# Breakout.net
KiCad netlist of a schematic drawn in EAGLE
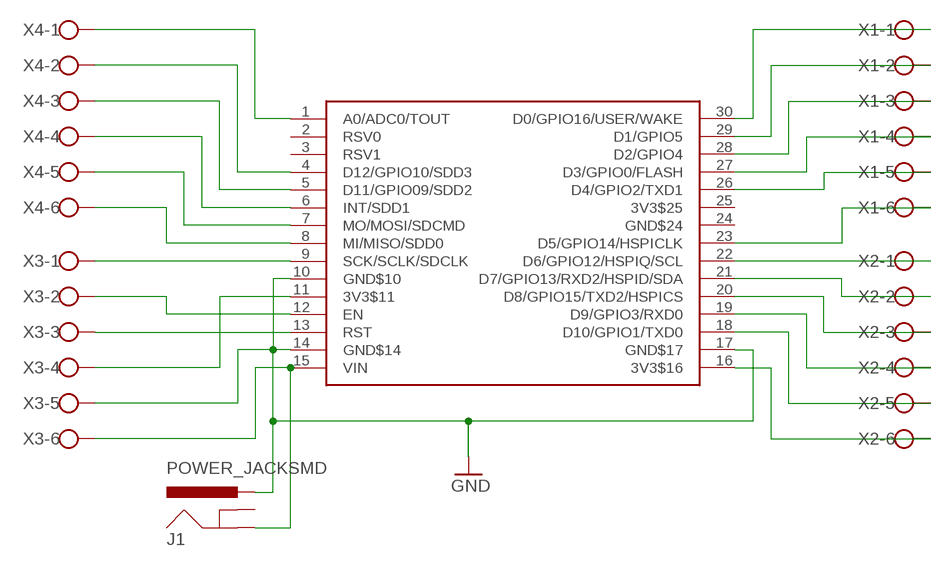
[diagram p0: schematic, sheet 1]

(export (version "E")
  (design (tool "Eeschema 10.0.6"))
  (components
    (comp (ref "J1")
      (value "POWER_JACKSMD")
      (footprint "eagle-import:POWER_JACK_SMD")
      (libsource (lib "eagle-import") (part "POWER_JACKSMD"))
    )
    (comp (ref "U$1")
      (value "NERDSHIELD")
      (footprint "eagle-import:NERDUINO_STACK")
      (libsource (lib "eagle-import") (part "NERDSHIELD"))
    )
    (comp (ref "X1")
      (value "W237-6")
      (footprint "eagle-import:W237-6")
      (libsource (lib "eagle-import") (part "W237-6"))
    )
    (comp (ref "X2")
      (value "W237-6")
      (footprint "eagle-import:W237-6")
      (libsource (lib "eagle-import") (part "W237-6"))
    )
    (comp (ref "X3")
      (value "W237-6")
      (footprint "eagle-import:W237-6")
      (libsource (lib "eagle-import") (part "W237-6"))
    )
    (comp (ref "X4")
      (value "W237-6")
      (footprint "eagle-import:W237-6")
      (libsource (lib "eagle-import") (part "W237-6"))
    )
  )
  (nets
    (net (code "1") (name "GND") (class "Default")
      (node (ref "J1") (pin "VIN0") (pinfunction "PWR_VIN0") (pintype "bidirectional"))
      (node (ref "U$1") (pin "10") (pinfunction "GND$10_10") (pintype "bidirectional"))
      (node (ref "U$1") (pin "14") (pinfunction "GND$14_14") (pintype "bidirectional"))
      (node (ref "U$1") (pin "17") (pinfunction "GND$17_17") (pintype "bidirectional"))
      (node (ref "X3") (pin "5") (pinfunction "KL_5") (pintype "passive"))
    )
    (net (code "2") (name "Net-(J1-GND)") (class "Default")
      (node (ref "J1") (pin "P$4") (pinfunction "GND_P$4") (pintype "bidirectional"))
      (node (ref "U$1") (pin "15") (pinfunction "VIN_15") (pintype "bidirectional"))
      (node (ref "X3") (pin "6") (pinfunction "KL_6") (pintype "passive"))
    )
    (net (code "3") (name "Net-(U$1-3V3$11)") (class "Default")
      (node (ref "U$1") (pin "11") (pinfunction "3V3$11_11") (pintype "bidirectional"))
      (node (ref "X3") (pin "4") (pinfunction "KL_4") (pintype "passive"))
    )
    (net (code "4") (name "Net-(U$1-3V3$16)") (class "Default")
      (node (ref "U$1") (pin "16") (pinfunction "3V3$16_16") (pintype "bidirectional"))
      (node (ref "X2") (pin "6") (pinfunction "KL_6") (pintype "passive"))
    )
    (net (code "5") (name "Net-(U$1-A0{slash}ADC0{slash}TOUT)") (class "Default")
      (node (ref "U$1") (pin "1") (pinfunction "A0/ADC0/TOUT_1") (pintype "bidirectional"))
      (node (ref "X4") (pin "1") (pinfunction "KL_1") (pintype "passive"))
    )
    (net (code "6") (name "Net-(U$1-D0{slash}GPIO16{slash}USER{slash}WAKE)") (class "Default")
      (node (ref "U$1") (pin "30") (pinfunction "D0/GPIO16/USER/WAKE_30") (pintype "bidirectional"))
      (node (ref "X1") (pin "1") (pinfunction "KL_1") (pintype "passive"))
    )
    (net (code "7") (name "Net-(U$1-D1{slash}GPIO5)") (class "Default")
      (node (ref "U$1") (pin "29") (pinfunction "D1/GPIO5_29") (pintype "bidirectional"))
      (node (ref "X1") (pin "2") (pinfunction "KL_2") (pintype "passive"))
    )
    (net (code "8") (name "Net-(U$1-D2{slash}GPIO4)") (class "Default")
      (node (ref "U$1") (pin "28") (pinfunction "D2/GPIO4_28") (pintype "bidirectional"))
      (node (ref "X1") (pin "3") (pinfunction "KL_3") (pintype "passive"))
    )
    (net (code "9") (name "Net-(U$1-D3{slash}GPIO0{slash}FLASH)") (class "Default")
      (node (ref "U$1") (pin "27") (pinfunction "D3/GPIO0/FLASH_27") (pintype "bidirectional"))
      (node (ref "X1") (pin "4") (pinfunction "KL_4") (pintype "passive"))
    )
    (net (code "10") (name "Net-(U$1-D4{slash}GPIO2{slash}TXD1)") (class "Default")
      (node (ref "U$1") (pin "26") (pinfunction "D4/GPIO2/TXD1_26") (pintype "bidirectional"))
      (node (ref "X1") (pin "5") (pinfunction "KL_5") (pintype "passive"))
    )
    (net (code "11") (name "Net-(U$1-D5{slash}GPIO14{slash}HSPICLK)") (class "Default")
      (node (ref "U$1") (pin "23") (pinfunction "D5/GPIO14/HSPICLK_23") (pintype "bidirectional"))
      (node (ref "X1") (pin "6") (pinfunction "KL_6") (pintype "passive"))
    )
    (net (code "12") (name "Net-(U$1-D6{slash}GPIO12{slash}HSPIQ{slash}SCL)") (class "Default")
      (node (ref "U$1") (pin "22") (pinfunction "D6/GPIO12/HSPIQ/SCL_22") (pintype "bidirectional"))
      (node (ref "X2") (pin "1") (pinfunction "KL_1") (pintype "passive"))
    )
    (net (code "13") (name "Net-(U$1-D7{slash}GPIO13{slash}RXD2{slash}HSPID{slash}SDA)") (class "Default")
      (node (ref "U$1") (pin "21") (pinfunction "D7/GPIO13/RXD2/HSPID/SDA_21") (pintype "bidirectional"))
      (node (ref "X2") (pin "2") (pinfunction "KL_2") (pintype "passive"))
    )
    (net (code "14") (name "Net-(U$1-D8{slash}GPIO15{slash}TXD2{slash}HSPICS)") (class "Default")
      (node (ref "U$1") (pin "20") (pinfunction "D8/GPIO15/TXD2/HSPICS_20") (pintype "bidirectional"))
      (node (ref "X2") (pin "3") (pinfunction "KL_3") (pintype "passive"))
    )
    (net (code "15") (name "Net-(U$1-D9{slash}GPIO3{slash}RXD0)") (class "Default")
      (node (ref "U$1") (pin "19") (pinfunction "D9/GPIO3/RXD0_19") (pintype "bidirectional"))
      (node (ref "X2") (pin "4") (pinfunction "KL_4") (pintype "passive"))
    )
    (net (code "16") (name "Net-(U$1-D10{slash}GPIO1{slash}TXD0)") (class "Default")
      (node (ref "U$1") (pin "18") (pinfunction "D10/GPIO1/TXD0_18") (pintype "bidirectional"))
      (node (ref "X2") (pin "5") (pinfunction "KL_5") (pintype "passive"))
    )
    (net (code "17") (name "Net-(U$1-D11{slash}GPIO09{slash}SDD2)") (class "Default")
      (node (ref "U$1") (pin "5") (pinfunction "D11/GPIO09/SDD2_5") (pintype "bidirectional"))
      (node (ref "X4") (pin "3") (pinfunction "KL_3") (pintype "passive"))
    )
    (net (code "18") (name "Net-(U$1-D12{slash}GPIO10{slash}SDD3)") (class "Default")
      (node (ref "U$1") (pin "4") (pinfunction "D12/GPIO10/SDD3_4") (pintype "bidirectional"))
      (node (ref "X4") (pin "2") (pinfunction "KL_2") (pintype "passive"))
    )
    (net (code "19") (name "Net-(U$1-EN)") (class "Default")
      (node (ref "U$1") (pin "12") (pinfunction "EN_12") (pintype "bidirectional"))
      (node (ref "X3") (pin "2") (pinfunction "KL_2") (pintype "passive"))
    )
    (net (code "20") (name "Net-(U$1-INT{slash}SDD1)") (class "Default")
      (node (ref "U$1") (pin "6") (pinfunction "INT/SDD1_6") (pintype "bidirectional"))
      (node (ref "X4") (pin "4") (pinfunction "KL_4") (pintype "passive"))
    )
    (net (code "21") (name "Net-(U$1-MI{slash}MISO{slash}SDD0)") (class "Default")
      (node (ref "U$1") (pin "8") (pinfunction "MI/MISO/SDD0_8") (pintype "bidirectional"))
      (node (ref "X4") (pin "6") (pinfunction "KL_6") (pintype "passive"))
    )
    (net (code "22") (name "Net-(U$1-MO{slash}MOSI{slash}SDCMD)") (class "Default")
      (node (ref "U$1") (pin "7") (pinfunction "MO/MOSI/SDCMD_7") (pintype "bidirectional"))
      (node (ref "X4") (pin "5") (pinfunction "KL_5") (pintype "passive"))
    )
    (net (code "23") (name "Net-(U$1-RST)") (class "Default")
      (node (ref "U$1") (pin "13") (pinfunction "RST_13") (pintype "bidirectional"))
      (node (ref "X3") (pin "3") (pinfunction "KL_3") (pintype "passive"))
    )
    (net (code "24") (name "Net-(U$1-SCK{slash}SCLK{slash}SDCLK)") (class "Default")
      (node (ref "U$1") (pin "9") (pinfunction "SCK/SCLK/SDCLK_9") (pintype "bidirectional"))
      (node (ref "X3") (pin "1") (pinfunction "KL_1") (pintype "passive"))
    )
    (net (code "25") (name "unconnected-(J1-GNDBREAK-PadGND)") (class "Default")
      (node (ref "J1") (pin "GND") (pinfunction "GNDBREAK_GND") (pintype "bidirectional"))
    )
    (net (code "26") (name "unconnected-(U$1-3V3$25-Pad25)") (class "Default")
      (node (ref "U$1") (pin "25") (pinfunction "3V3$25_25") (pintype "bidirectional"))
    )
    (net (code "27") (name "unconnected-(U$1-GND$24-Pad24)") (class "Default")
      (node (ref "U$1") (pin "24") (pinfunction "GND$24_24") (pintype "bidirectional"))
    )
    (net (code "28") (name "unconnected-(U$1-RSV0-Pad2)") (class "Default")
      (node (ref "U$1") (pin "2") (pinfunction "RSV0_2") (pintype "bidirectional"))
    )
    (net (code "29") (name "unconnected-(U$1-RSV1-Pad3)") (class "Default")
      (node (ref "U$1") (pin "3") (pinfunction "RSV1_3") (pintype "bidirectional"))
    )
  )
)
